# Mcu.net
KiCad netlist of a schematic drawn in Altium Designer
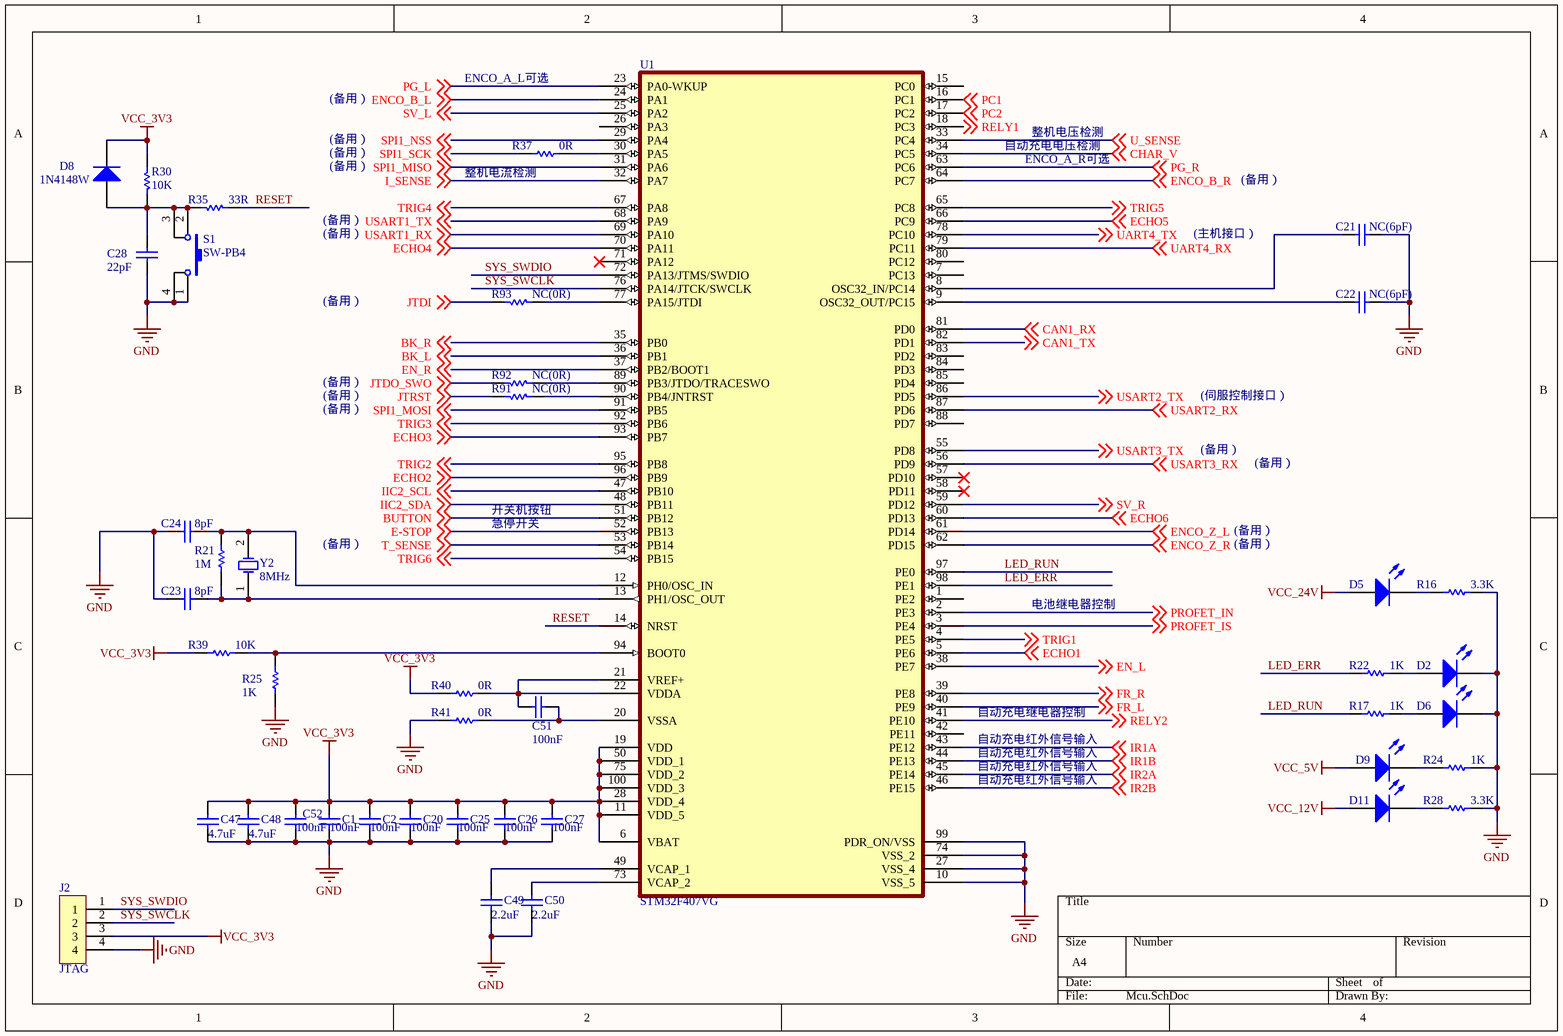
[diagram p0: Mcu.SchDoc]

(export (version "E")
  (design (tool "Eeschema 10.0.6"))
  (components
    (comp (ref "C1")
      (value "100nF")
      (footprint "C0805")
      (description "Capacitor")
      (fields (field (name "Comment") "Cap") (field (name "PUBLISHER") "Altium Limited"))
      (libsource (lib "boocax_schlib") (part "Cap"))
    )
    (comp (ref "C2")
      (value "100nF")
      (footprint "C0805")
      (description "Capacitor")
      (fields (field (name "Comment") "Cap") (field (name "PUBLISHER") "Altium Limited"))
      (libsource (lib "boocax_schlib") (part "Cap"))
    )
    (comp (ref "C20")
      (value "100nF")
      (footprint "C0805")
      (description "Capacitor")
      (fields (field (name "Comment") "Cap") (field (name "PUBLISHER") "Altium Limited"))
      (libsource (lib "boocax_schlib") (part "Cap"))
    )
    (comp (ref "C21")
      (value "NC(6pF)")
      (footprint "C0805")
      (description "Capacitor")
      (fields (field (name "PUBLISHER") "Altium Limited"))
      (libsource (lib "Miscellaneous Devices") (part "Cap"))
    )
    (comp (ref "C22")
      (value "NC(6pF)")
      (footprint "C0805")
      (description "Capacitor")
      (fields (field (name "PUBLISHER") "Altium Limited"))
      (libsource (lib "Miscellaneous Devices") (part "Cap"))
    )
    (comp (ref "C23")
      (value "8pF")
      (footprint "C0805")
      (description "Capacitor")
      (fields (field (name "PUBLISHER") "Altium Limited"))
      (libsource (lib "Miscellaneous Devices") (part "Cap"))
    )
    (comp (ref "C24")
      (value "8pF")
      (footprint "C0805")
      (description "Capacitor")
      (fields (field (name "PUBLISHER") "Altium Limited"))
      (libsource (lib "Miscellaneous Devices") (part "Cap"))
    )
    (comp (ref "C25")
      (value "100nF")
      (footprint "C0805")
      (description "Capacitor")
      (fields (field (name "Comment") "Cap") (field (name "PUBLISHER") "Altium Limited"))
      (libsource (lib "boocax_schlib") (part "Cap"))
    )
    (comp (ref "C26")
      (value "100nF")
      (footprint "C0805")
      (description "Capacitor")
      (fields (field (name "Comment") "Cap") (field (name "PUBLISHER") "Altium Limited"))
      (libsource (lib "boocax_schlib") (part "Cap"))
    )
    (comp (ref "C27")
      (value "100nF")
      (footprint "C0805")
      (description "Capacitor")
      (fields (field (name "Comment") "Cap") (field (name "PUBLISHER") "Altium Limited"))
      (libsource (lib "boocax_schlib") (part "Cap"))
    )
    (comp (ref "C28")
      (value "22pF")
      (footprint "C0805")
      (description "Capacitor")
      (fields (field (name "Comment") "Cap") (field (name "PUBLISHER") "Altium Limited"))
      (libsource (lib "boocax_schlib") (part "Cap"))
    )
    (comp (ref "C47")
      (value "4.7uF")
      (footprint "C0805")
      (description "Capacitor")
      (fields (field (name "Comment") "Cap") (field (name "PUBLISHER") "Altium Limited"))
      (libsource (lib "boocax_schlib") (part "Cap"))
    )
    (comp (ref "C48")
      (value "4.7uF")
      (footprint "C0805")
      (description "Capacitor")
      (fields (field (name "Comment") "Cap") (field (name "PUBLISHER") "Altium Limited"))
      (libsource (lib "boocax_schlib") (part "Cap"))
    )
    (comp (ref "C49")
      (value "2.2uF")
      (footprint "C0805")
      (description "Capacitor")
      (fields (field (name "Comment") "Cap") (field (name "PUBLISHER") "Altium Limited"))
      (libsource (lib "boocax_schlib") (part "Cap"))
    )
    (comp (ref "C50")
      (value "2.2uF")
      (footprint "C0805")
      (description "Capacitor")
      (fields (field (name "Comment") "Cap") (field (name "PUBLISHER") "Altium Limited"))
      (libsource (lib "boocax_schlib") (part "Cap"))
    )
    (comp (ref "C51")
      (value "100nF")
      (footprint "C0805")
      (description "Capacitor")
      (fields (field (name "Comment") "Cap") (field (name "PUBLISHER") "Altium Limited"))
      (libsource (lib "boocax_schlib") (part "Cap"))
    )
    (comp (ref "C52")
      (value "100nF")
      (footprint "C0805")
      (description "Capacitor")
      (fields (field (name "Comment") "Cap") (field (name "PUBLISHER") "Altium Limited"))
      (libsource (lib "boocax_schlib") (part "Cap"))
    )
    (comp (ref "D2")
      (value "LED0")
      (footprint "LED-H-R2.54")
      (description "发光二极管")
      (fields (field (name "PUBLISHER") "Altium Limited"))
      (libsource (lib "founder") (part "LED0"))
    )
    (comp (ref "D5")
      (value "LED0")
      (footprint "LED-H-R2.54")
      (description "发光二极管")
      (fields (field (name "PUBLISHER") "Altium Limited"))
      (libsource (lib "founder") (part "LED0"))
    )
    (comp (ref "D6")
      (value "LED0")
      (footprint "LED-H-R2.54")
      (description "发光二极管")
      (fields (field (name "PUBLISHER") "Altium Limited"))
      (libsource (lib "founder") (part "LED0"))
    )
    (comp (ref "D8")
      (value "1N4148W")
      (footprint "1206")
      (description "二极管")
      (fields (field (name "Comment") "Diode") (field (name "PUBLISHER") "Altium Limited"))
      (libsource (lib "founder") (part "Diode"))
    )
    (comp (ref "D9")
      (value "LED0")
      (footprint "LED-H-R2.54")
      (description "发光二极管")
      (fields (field (name "PUBLISHER") "Altium Limited"))
      (libsource (lib "founder") (part "LED0"))
    )
    (comp (ref "D11")
      (value "LED0")
      (footprint "LED-H-R2.54")
      (description "发光二极管")
      (fields (field (name "PUBLISHER") "Altium Limited"))
      (libsource (lib "founder") (part "LED0"))
    )
    (comp (ref "J2")
      (value "JTAG")
      (footprint "PORT-SIP4-2.54")
      (libsource (lib "boocax_schlib") (part "Conn_1*4_1"))
    )
    (comp (ref "R16")
      (value "3.3K")
      (footprint "R0805")
      (description "Resistor")
      (fields (field (name "Comment") "Res1") (field (name "PUBLISHER") "Altium Limited"))
      (libsource (lib "boocax_schlib") (part "Res1"))
    )
    (comp (ref "R17")
      (value "1K")
      (footprint "R0805")
      (description "Resistor")
      (fields (field (name "Comment") "Res1") (field (name "PUBLISHER") "Altium Limited"))
      (libsource (lib "boocax_schlib") (part "Res1"))
    )
    (comp (ref "R21")
      (value "1M")
      (footprint "R0805")
      (description "Resistor")
      (fields (field (name "Comment") "Res1") (field (name "PUBLISHER") "Altium Limited"))
      (libsource (lib "boocax_schlib") (part "Res1"))
    )
    (comp (ref "R22")
      (value "1K")
      (footprint "R0805")
      (description "Resistor")
      (fields (field (name "Comment") "Res1") (field (name "PUBLISHER") "Altium Limited"))
      (libsource (lib "boocax_schlib") (part "Res1"))
    )
    (comp (ref "R24")
      (value "1K")
      (footprint "R0805")
      (description "Resistor")
      (fields (field (name "Comment") "Res1") (field (name "PUBLISHER") "Altium Limited"))
      (libsource (lib "boocax_schlib") (part "Res1"))
    )
    (comp (ref "R25")
      (value "1K")
      (footprint "R0805")
      (description "Resistor")
      (fields (field (name "Comment") "Res1") (field (name "PUBLISHER") "Altium Limited"))
      (libsource (lib "boocax_schlib") (part "Res1"))
    )
    (comp (ref "R28")
      (value "3.3K")
      (footprint "R0805")
      (description "Resistor")
      (fields (field (name "Comment") "Res1") (field (name "PUBLISHER") "Altium Limited"))
      (libsource (lib "boocax_schlib") (part "Res1"))
    )
    (comp (ref "R30")
      (value "10K")
      (footprint "R0805")
      (description "Resistor")
      (fields (field (name "Comment") "Res1") (field (name "PUBLISHER") "Altium Limited"))
      (libsource (lib "boocax_schlib") (part "Res1"))
    )
    (comp (ref "R35")
      (value "33R")
      (footprint "R0805")
      (description "Resistor")
      (fields (field (name "Comment") "Res1") (field (name "PUBLISHER") "Altium Limited"))
      (libsource (lib "boocax_schlib") (part "Res1"))
    )
    (comp (ref "R37")
      (value "0R")
      (footprint "R0805")
      (description "Resistor")
      (fields (field (name "Comment") "Res1") (field (name "PUBLISHER") "Altium Limited"))
      (libsource (lib "boocax_schlib") (part "Res1"))
    )
    (comp (ref "R39")
      (value "10K")
      (footprint "R0805")
      (description "Resistor")
      (fields (field (name "Comment") "Res1") (field (name "PUBLISHER") "Altium Limited"))
      (libsource (lib "boocax_schlib") (part "Res1"))
    )
    (comp (ref "R40")
      (value "0R")
      (footprint "R0805")
      (description "Resistor")
      (fields (field (name "Comment") "Res1") (field (name "PUBLISHER") "Altium Limited"))
      (libsource (lib "boocax_schlib") (part "Res1"))
    )
    (comp (ref "R41")
      (value "0R")
      (footprint "R0805")
      (description "Resistor")
      (fields (field (name "Comment") "Res1") (field (name "PUBLISHER") "Altium Limited"))
      (libsource (lib "boocax_schlib") (part "Res1"))
    )
    (comp (ref "R91")
      (value "NC(0R)")
      (footprint "R0805")
      (description "Resistor")
      (fields (field (name "Comment") "Res1") (field (name "PUBLISHER") "Altium Limited"))
      (libsource (lib "boocax_schlib") (part "Res1"))
    )
    (comp (ref "R92")
      (value "NC(0R)")
      (footprint "R0805")
      (description "Resistor")
      (fields (field (name "Comment") "Res1") (field (name "PUBLISHER") "Altium Limited"))
      (libsource (lib "boocax_schlib") (part "Res1"))
    )
    (comp (ref "R93")
      (value "NC(0R)")
      (footprint "R0805")
      (description "Resistor")
      (fields (field (name "Comment") "Res1") (field (name "PUBLISHER") "Altium Limited"))
      (libsource (lib "boocax_schlib") (part "Res1"))
    )
    (comp (ref "S1")
      (value "SW-PB4")
      (footprint "RESET-SMD-1O4")
      (description "微动开关")
      (fields (field (name "PUBLISHER") "Altium Limited"))
      (libsource (lib "boocax_schlib") (part "SW-PB4"))
    )
    (comp (ref "U1")
      (value "STM32F407VG")
      (footprint "boocax_schlib:100T1_N")
      (libsource (lib "boocax_schlib") (part "STM32F407VG"))
    )
    (comp (ref "Y2")
      (value "8MHz")
      (footprint "CLK_3.1")
      (description "X1A0000610030xx")
      (fields (field (name "PUBLISHER") "Altium Limited"))
      (libsource (lib "Miscellaneous Devices") (part "XTAL"))
    )
  )
  (nets
    (net (code "1") (name "/LED_ERR") (class "Default")
      (node (ref "R22") (pin "2") (pinfunction "2_2") (pintype "passive"))
      (node (ref "U1") (pin "98") (pinfunction "PE1_98") (pintype "bidirectional"))
    )
    (net (code "2") (name "/LED_RUN") (class "Default")
      (node (ref "R17") (pin "2") (pinfunction "2_2") (pintype "passive"))
      (node (ref "U1") (pin "97") (pinfunction "PE0_97") (pintype "bidirectional"))
    )
    (net (code "3") (name "/RESET") (class "Default")
      (node (ref "R35") (pin "1") (pinfunction "1_1") (pintype "passive"))
      (node (ref "U1") (pin "14") (pinfunction "NRST_14") (pintype "bidirectional"))
    )
    (net (code "4") (name "/SYS_SWCLK") (class "Default")
      (node (ref "J2") (pin "2") (pinfunction "2_2") (pintype "passive"))
      (node (ref "U1") (pin "76") (pinfunction "PA14/JTCK/SWCLK_76") (pintype "bidirectional"))
    )
    (net (code "5") (name "/SYS_SWDIO") (class "Default")
      (node (ref "J2") (pin "1") (pinfunction "1_1") (pintype "passive"))
      (node (ref "U1") (pin "72") (pinfunction "PA13/JTMS/SWDIO_72") (pintype "bidirectional"))
    )
    (net (code "6") (name "BK_L") (class "Default")
      (node (ref "U1") (pin "36") (pinfunction "PB1_36") (pintype "bidirectional"))
    )
    (net (code "7") (name "BK_R") (class "Default")
      (node (ref "U1") (pin "35") (pinfunction "PB0_35") (pintype "bidirectional"))
    )
    (net (code "8") (name "BUTTON") (class "Default")
      (node (ref "U1") (pin "51") (pinfunction "PB12_51") (pintype "bidirectional"))
    )
    (net (code "9") (name "CAN1_RX") (class "Default")
      (node (ref "U1") (pin "81") (pinfunction "PD0_81") (pintype "bidirectional"))
    )
    (net (code "10") (name "CAN1_TX") (class "Default")
      (node (ref "U1") (pin "82") (pinfunction "PD1_82") (pintype "bidirectional"))
    )
    (net (code "11") (name "CHAR_V") (class "Default")
      (node (ref "U1") (pin "34") (pinfunction "PC5_34") (pintype "bidirectional"))
    )
    (net (code "12") (name "E-STOP") (class "Default")
      (node (ref "U1") (pin "52") (pinfunction "PB13_52") (pintype "bidirectional"))
    )
    (net (code "13") (name "ECHO1") (class "Default")
      (node (ref "U1") (pin "5") (pinfunction "PE6_5") (pintype "bidirectional"))
    )
    (net (code "14") (name "ECHO2") (class "Default")
      (node (ref "U1") (pin "96") (pinfunction "PB9_96") (pintype "bidirectional"))
    )
    (net (code "15") (name "ECHO3") (class "Default")
      (node (ref "U1") (pin "93") (pinfunction "PB7_93") (pintype "bidirectional"))
    )
    (net (code "16") (name "ECHO4") (class "Default")
      (node (ref "U1") (pin "70") (pinfunction "PA11_70") (pintype "bidirectional"))
    )
    (net (code "17") (name "ECHO5") (class "Default")
      (node (ref "U1") (pin "66") (pinfunction "PC9_66") (pintype "bidirectional"))
    )
    (net (code "18") (name "ECHO6") (class "Default")
      (node (ref "U1") (pin "60") (pinfunction "PD13_60") (pintype "bidirectional"))
    )
    (net (code "19") (name "ENCO_B_L") (class "Default")
      (node (ref "U1") (pin "24") (pinfunction "PA1_24") (pintype "bidirectional"))
    )
    (net (code "20") (name "ENCO_B_R") (class "Default")
      (node (ref "U1") (pin "64") (pinfunction "PC7_64") (pintype "bidirectional"))
    )
    (net (code "21") (name "ENCO_Z_L") (class "Default")
      (node (ref "U1") (pin "61") (pinfunction "PD14_61") (pintype "bidirectional"))
    )
    (net (code "22") (name "ENCO_Z_R") (class "Default")
      (node (ref "U1") (pin "62") (pinfunction "PD15_62") (pintype "bidirectional"))
    )
    (net (code "23") (name "EN_L") (class "Default")
      (node (ref "U1") (pin "38") (pinfunction "PE7_38") (pintype "bidirectional"))
    )
    (net (code "24") (name "EN_R") (class "Default")
      (node (ref "U1") (pin "37") (pinfunction "PB2/BOOT1_37") (pintype "bidirectional"))
    )
    (net (code "25") (name "FR_L") (class "Default")
      (node (ref "U1") (pin "40") (pinfunction "PE9_40") (pintype "bidirectional"))
    )
    (net (code "26") (name "FR_R") (class "Default")
      (node (ref "U1") (pin "39") (pinfunction "PE8_39") (pintype "bidirectional"))
    )
    (net (code "27") (name "GND") (class "Default")
      (node (ref "C1") (pin "2") (pinfunction "2_2") (pintype "passive"))
      (node (ref "C2") (pin "2") (pinfunction "2_2") (pintype "passive"))
      (node (ref "C20") (pin "2") (pinfunction "2_2") (pintype "passive"))
      (node (ref "C21") (pin "1") (pinfunction "1_1") (pintype "passive"))
      (node (ref "C22") (pin "1") (pinfunction "1_1") (pintype "passive"))
      (node (ref "C23") (pin "2") (pinfunction "2_2") (pintype "passive"))
      (node (ref "C24") (pin "2") (pinfunction "2_2") (pintype "passive"))
      (node (ref "C25") (pin "2") (pinfunction "2_2") (pintype "passive"))
      (node (ref "C26") (pin "2") (pinfunction "2_2") (pintype "passive"))
      (node (ref "C27") (pin "2") (pinfunction "2_2") (pintype "passive"))
      (node (ref "C28") (pin "1") (pinfunction "1_1") (pintype "passive"))
      (node (ref "C47") (pin "2") (pinfunction "2_2") (pintype "passive"))
      (node (ref "C48") (pin "2") (pinfunction "2_2") (pintype "passive"))
      (node (ref "C49") (pin "2") (pinfunction "2_2") (pintype "passive"))
      (node (ref "C50") (pin "2") (pinfunction "2_2") (pintype "passive"))
      (node (ref "C52") (pin "2") (pinfunction "2_2") (pintype "passive"))
      (node (ref "D2") (pin "2") (pinfunction "K_2") (pintype "passive"))
      (node (ref "D6") (pin "2") (pinfunction "K_2") (pintype "passive"))
      (node (ref "J2") (pin "4") (pinfunction "4_4") (pintype "passive"))
      (node (ref "R16") (pin "1") (pinfunction "1_1") (pintype "passive"))
      (node (ref "R24") (pin "1") (pinfunction "1_1") (pintype "passive"))
      (node (ref "R25") (pin "1") (pinfunction "1_1") (pintype "passive"))
      (node (ref "R28") (pin "1") (pinfunction "1_1") (pintype "passive"))
      (node (ref "R41") (pin "2") (pinfunction "2_2") (pintype "passive"))
      (node (ref "S1") (pin "1") (pinfunction "1_1") (pintype "passive"))
      (node (ref "S1") (pin "4") (pinfunction "4_4") (pintype "passive"))
      (node (ref "U1") (pin "10") (pinfunction "VSS_5_10") (pintype "passive"))
      (node (ref "U1") (pin "27") (pinfunction "VSS_4_27") (pintype "passive"))
      (node (ref "U1") (pin "74") (pinfunction "VSS_2_74") (pintype "passive"))
      (node (ref "U1") (pin "99") (pinfunction "PDR_ON/VSS_99") (pintype "power_in"))
    )
    (net (code "28") (name "IIC2_SCL") (class "Default")
      (node (ref "U1") (pin "47") (pinfunction "PB10_47") (pintype "bidirectional"))
    )
    (net (code "29") (name "IIC2_SDA") (class "Default")
      (node (ref "U1") (pin "48") (pinfunction "PB11_48") (pintype "bidirectional"))
    )
    (net (code "30") (name "IR1A") (class "Default")
      (node (ref "U1") (pin "43") (pinfunction "PE12_43") (pintype "bidirectional"))
    )
    (net (code "31") (name "IR1B") (class "Default")
      (node (ref "U1") (pin "44") (pinfunction "PE13_44") (pintype "bidirectional"))
    )
    (net (code "32") (name "IR2A") (class "Default")
      (node (ref "U1") (pin "45") (pinfunction "PE14_45") (pintype "bidirectional"))
    )
    (net (code "33") (name "IR2B") (class "Default")
      (node (ref "U1") (pin "46") (pinfunction "PE15_46") (pintype "bidirectional"))
    )
    (net (code "34") (name "I_SENSE") (class "Default")
      (node (ref "U1") (pin "32") (pinfunction "PA7_32") (pintype "bidirectional"))
    )
    (net (code "35") (name "JTDI") (class "Default")
      (node (ref "R93") (pin "2") (pinfunction "2_2") (pintype "passive"))
    )
    (net (code "36") (name "JTDO_SWO") (class "Default")
      (node (ref "R92") (pin "2") (pinfunction "2_2") (pintype "passive"))
    )
    (net (code "37") (name "JTRST") (class "Default")
      (node (ref "R91") (pin "2") (pinfunction "2_2") (pintype "passive"))
    )
    (net (code "38") (name "Net-(D2-A)") (class "Default")
      (node (ref "D2") (pin "1") (pinfunction "A_1") (pintype "passive"))
      (node (ref "R22") (pin "1") (pinfunction "1_1") (pintype "passive"))
    )
    (net (code "39") (name "Net-(D5-K)") (class "Default")
      (node (ref "D5") (pin "2") (pinfunction "K_2") (pintype "passive"))
      (node (ref "R16") (pin "2") (pinfunction "2_2") (pintype "passive"))
    )
    (net (code "40") (name "Net-(D6-A)") (class "Default")
      (node (ref "D6") (pin "1") (pinfunction "A_1") (pintype "passive"))
      (node (ref "R17") (pin "1") (pinfunction "1_1") (pintype "passive"))
    )
    (net (code "41") (name "Net-(D8-A)") (class "Default")
      (node (ref "C28") (pin "2") (pinfunction "2_2") (pintype "passive"))
      (node (ref "D8") (pin "1") (pinfunction "A_1") (pintype "passive"))
      (node (ref "R30") (pin "1") (pinfunction "1_1") (pintype "passive"))
      (node (ref "R35") (pin "2") (pinfunction "2_2") (pintype "passive"))
      (node (ref "S1") (pin "2") (pinfunction "2_2") (pintype "passive"))
      (node (ref "S1") (pin "3") (pinfunction "3_3") (pintype "passive"))
    )
    (net (code "42") (name "Net-(D9-K)") (class "Default")
      (node (ref "D9") (pin "2") (pinfunction "K_2") (pintype "passive"))
      (node (ref "R24") (pin "2") (pinfunction "2_2") (pintype "passive"))
    )
    (net (code "43") (name "Net-(D11-K)") (class "Default")
      (node (ref "D11") (pin "2") (pinfunction "K_2") (pintype "passive"))
      (node (ref "R28") (pin "2") (pinfunction "2_2") (pintype "passive"))
    )
    (net (code "44") (name "Net-(U1-BOOT0)") (class "Default")
      (node (ref "R25") (pin "2") (pinfunction "2_2") (pintype "passive"))
      (node (ref "R39") (pin "1") (pinfunction "1_1") (pintype "passive"))
      (node (ref "U1") (pin "94") (pinfunction "BOOT0_94") (pintype "input"))
    )
    (net (code "45") (name "Net-(U1-OSC32_IN{slash}PC14)") (class "Default")
      (node (ref "C21") (pin "2") (pinfunction "2_2") (pintype "passive"))
      (node (ref "U1") (pin "8") (pinfunction "OSC32_IN/PC14_8") (pintype "bidirectional"))
    )
    (net (code "46") (name "Net-(U1-OSC32_OUT{slash}PC15)") (class "Default")
      (node (ref "C22") (pin "2") (pinfunction "2_2") (pintype "passive"))
      (node (ref "U1") (pin "9") (pinfunction "OSC32_OUT/PC15_9") (pintype "bidirectional"))
    )
    (net (code "47") (name "Net-(U1-PA5)") (class "Default")
      (node (ref "R37") (pin "1") (pinfunction "1_1") (pintype "passive"))
      (node (ref "U1") (pin "30") (pinfunction "PA5_30") (pintype "bidirectional"))
    )
    (net (code "48") (name "Net-(U1-PA15{slash}JTDI)") (class "Default")
      (node (ref "R93") (pin "1") (pinfunction "1_1") (pintype "passive"))
      (node (ref "U1") (pin "77") (pinfunction "PA15/JTDI_77") (pintype "bidirectional"))
    )
    (net (code "49") (name "Net-(U1-PB3{slash}JTDO{slash}TRACESWO)") (class "Default")
      (node (ref "R92") (pin "1") (pinfunction "1_1") (pintype "passive"))
      (node (ref "U1") (pin "89") (pinfunction "PB3/JTDO/TRACESWO_89") (pintype "bidirectional"))
    )
    (net (code "50") (name "Net-(U1-PB4{slash}JNTRST)") (class "Default")
      (node (ref "R91") (pin "1") (pinfunction "1_1") (pintype "passive"))
      (node (ref "U1") (pin "90") (pinfunction "PB4/JNTRST_90") (pintype "bidirectional"))
    )
    (net (code "51") (name "Net-(U1-PH0{slash}OSC_IN)") (class "Default")
      (node (ref "C24") (pin "1") (pinfunction "1_1") (pintype "passive"))
      (node (ref "R21") (pin "2") (pinfunction "2_2") (pintype "passive"))
      (node (ref "U1") (pin "12") (pinfunction "PH0/OSC_IN_12") (pintype "input"))
      (node (ref "Y2") (pin "2") (pinfunction "OSC2_2") (pintype "passive"))
    )
    (net (code "52") (name "Net-(U1-PH1{slash}OSC_OUT)") (class "Default")
      (node (ref "C23") (pin "1") (pinfunction "1_1") (pintype "passive"))
      (node (ref "R21") (pin "1") (pinfunction "1_1") (pintype "passive"))
      (node (ref "U1") (pin "13") (pinfunction "PH1/OSC_OUT_13") (pintype "output"))
      (node (ref "Y2") (pin "1") (pinfunction "OSC1_1") (pintype "passive"))
    )
    (net (code "53") (name "Net-(U1-VCAP_1)") (class "Default")
      (node (ref "C49") (pin "1") (pinfunction "1_1") (pintype "passive"))
      (node (ref "U1") (pin "49") (pinfunction "VCAP_1_49") (pintype "power_in"))
    )
    (net (code "54") (name "Net-(U1-VCAP_2)") (class "Default")
      (node (ref "C50") (pin "1") (pinfunction "1_1") (pintype "passive"))
      (node (ref "U1") (pin "73") (pinfunction "VCAP_2_73") (pintype "power_in"))
    )
    (net (code "55") (name "Net-(U1-VDDA)") (class "Default")
      (node (ref "C51") (pin "1") (pinfunction "1_1") (pintype "passive"))
      (node (ref "R40") (pin "1") (pinfunction "1_1") (pintype "passive"))
      (node (ref "U1") (pin "21") (pinfunction "VREF+_21") (pintype "power_in"))
      (node (ref "U1") (pin "22") (pinfunction "VDDA_22") (pintype "power_in"))
    )
    (net (code "56") (name "Net-(U1-VSSA)") (class "Default")
      (node (ref "C51") (pin "2") (pinfunction "2_2") (pintype "passive"))
      (node (ref "R41") (pin "1") (pinfunction "1_1") (pintype "passive"))
      (node (ref "U1") (pin "20") (pinfunction "VSSA_20") (pintype "power_in"))
    )
    (net (code "57") (name "PC1") (class "Default")
      (node (ref "U1") (pin "16") (pinfunction "PC1_16") (pintype "bidirectional"))
    )
    (net (code "58") (name "PC2") (class "Default")
      (node (ref "U1") (pin "17") (pinfunction "PC2_17") (pintype "bidirectional"))
    )
    (net (code "59") (name "PG_L") (class "Default")
      (node (ref "U1") (pin "23") (pinfunction "PA0-WKUP_23") (pintype "bidirectional"))
    )
    (net (code "60") (name "PG_R") (class "Default")
      (node (ref "U1") (pin "63") (pinfunction "PC6_63") (pintype "bidirectional"))
    )
    (net (code "61") (name "PROFET_IN") (class "Default")
      (node (ref "U1") (pin "2") (pinfunction "PE3_2") (pintype "bidirectional"))
    )
    (net (code "62") (name "PROFET_IS") (class "Default")
      (node (ref "U1") (pin "3") (pinfunction "PE4_3") (pintype "bidirectional"))
    )
    (net (code "63") (name "RELY1") (class "Default")
      (node (ref "U1") (pin "18") (pinfunction "PC3_18") (pintype "bidirectional"))
    )
    (net (code "64") (name "RELY2") (class "Default")
      (node (ref "U1") (pin "41") (pinfunction "PE10_41") (pintype "bidirectional"))
    )
    (net (code "65") (name "SPI1_MISO") (class "Default")
      (node (ref "U1") (pin "31") (pinfunction "PA6_31") (pintype "bidirectional"))
    )
    (net (code "66") (name "SPI1_MOSI") (class "Default")
      (node (ref "U1") (pin "91") (pinfunction "PB5_91") (pintype "bidirectional"))
    )
    (net (code "67") (name "SPI1_NSS") (class "Default")
      (node (ref "U1") (pin "29") (pinfunction "PA4_29") (pintype "bidirectional"))
    )
    (net (code "68") (name "SPI1_SCK") (class "Default")
      (node (ref "R37") (pin "2") (pinfunction "2_2") (pintype "passive"))
    )
    (net (code "69") (name "SV_L") (class "Default")
      (node (ref "U1") (pin "25") (pinfunction "PA2_25") (pintype "bidirectional"))
    )
    (net (code "70") (name "SV_R") (class "Default")
      (node (ref "U1") (pin "59") (pinfunction "PD12_59") (pintype "bidirectional"))
    )
    (net (code "71") (name "TRIG1") (class "Default")
      (node (ref "U1") (pin "4") (pinfunction "PE5_4") (pintype "bidirectional"))
    )
    (net (code "72") (name "TRIG2") (class "Default")
      (node (ref "U1") (pin "95") (pinfunction "PB8_95") (pintype "bidirectional"))
    )
    (net (code "73") (name "TRIG3") (class "Default")
      (node (ref "U1") (pin "92") (pinfunction "PB6_92") (pintype "bidirectional"))
    )
    (net (code "74") (name "TRIG4") (class "Default")
      (node (ref "U1") (pin "67") (pinfunction "PA8_67") (pintype "bidirectional"))
    )
    (net (code "75") (name "TRIG5") (class "Default")
      (node (ref "U1") (pin "65") (pinfunction "PC8_65") (pintype "bidirectional"))
    )
    (net (code "76") (name "TRIG6") (class "Default")
      (node (ref "U1") (pin "54") (pinfunction "PB15_54") (pintype "bidirectional"))
    )
    (net (code "77") (name "T_SENSE") (class "Default")
      (node (ref "U1") (pin "53") (pinfunction "PB14_53") (pintype "bidirectional"))
    )
    (net (code "78") (name "UART4_RX") (class "Default")
      (node (ref "U1") (pin "79") (pinfunction "PC11_79") (pintype "bidirectional"))
    )
    (net (code "79") (name "UART4_TX") (class "Default")
      (node (ref "U1") (pin "78") (pinfunction "PC10_78") (pintype "bidirectional"))
    )
    (net (code "80") (name "USART1_RX") (class "Default")
      (node (ref "U1") (pin "69") (pinfunction "PA10_69") (pintype "bidirectional"))
    )
    (net (code "81") (name "USART1_TX") (class "Default")
      (node (ref "U1") (pin "68") (pinfunction "PA9_68") (pintype "bidirectional"))
    )
    (net (code "82") (name "USART2_RX") (class "Default")
      (node (ref "U1") (pin "87") (pinfunction "PD6_87") (pintype "bidirectional"))
    )
    (net (code "83") (name "USART2_TX") (class "Default")
      (node (ref "U1") (pin "86") (pinfunction "PD5_86") (pintype "bidirectional"))
    )
    (net (code "84") (name "USART3_RX") (class "Default")
      (node (ref "U1") (pin "56") (pinfunction "PD9_56") (pintype "bidirectional"))
    )
    (net (code "85") (name "USART3_TX") (class "Default")
      (node (ref "U1") (pin "55") (pinfunction "PD8_55") (pintype "bidirectional"))
    )
    (net (code "86") (name "U_SENSE") (class "Default")
      (node (ref "U1") (pin "33") (pinfunction "PC4_33") (pintype "bidirectional"))
    )
    (net (code "87") (name "VCC_3V3") (class "Default")
      (node (ref "C1") (pin "1") (pinfunction "1_1") (pintype "passive"))
      (node (ref "C2") (pin "1") (pinfunction "1_1") (pintype "passive"))
      (node (ref "C20") (pin "1") (pinfunction "1_1") (pintype "passive"))
      (node (ref "C25") (pin "1") (pinfunction "1_1") (pintype "passive"))
      (node (ref "C26") (pin "1") (pinfunction "1_1") (pintype "passive"))
      (node (ref "C27") (pin "1") (pinfunction "1_1") (pintype "passive"))
      (node (ref "C47") (pin "1") (pinfunction "1_1") (pintype "passive"))
      (node (ref "C48") (pin "1") (pinfunction "1_1") (pintype "passive"))
      (node (ref "C52") (pin "1") (pinfunction "1_1") (pintype "passive"))
      (node (ref "D8") (pin "2") (pinfunction "K_2") (pintype "passive"))
      (node (ref "J2") (pin "3") (pinfunction "3_3") (pintype "passive"))
      (node (ref "R30") (pin "2") (pinfunction "2_2") (pintype "passive"))
      (node (ref "R39") (pin "2") (pinfunction "2_2") (pintype "passive"))
      (node (ref "R40") (pin "2") (pinfunction "2_2") (pintype "passive"))
      (node (ref "U1") (pin "100") (pinfunction "VDD_3_100") (pintype "power_in"))
      (node (ref "U1") (pin "11") (pinfunction "VDD_5_11") (pintype "power_in"))
      (node (ref "U1") (pin "19") (pinfunction "VDD_19") (pintype "power_in"))
      (node (ref "U1") (pin "28") (pinfunction "VDD_4_28") (pintype "power_in"))
      (node (ref "U1") (pin "50") (pinfunction "VDD_1_50") (pintype "power_in"))
      (node (ref "U1") (pin "6") (pinfunction "VBAT_6") (pintype "power_in"))
      (node (ref "U1") (pin "75") (pinfunction "VDD_2_75") (pintype "power_in"))
    )
    (net (code "88") (name "VCC_5V") (class "Default")
      (node (ref "D9") (pin "1") (pinfunction "A_1") (pintype "passive"))
    )
    (net (code "89") (name "VCC_12V") (class "Default")
      (node (ref "D11") (pin "1") (pinfunction "A_1") (pintype "passive"))
    )
    (net (code "90") (name "VCC_24V") (class "Default")
      (node (ref "D5") (pin "1") (pinfunction "A_1") (pintype "passive"))
    )
    (net (code "91") (name "unconnected-(U1-PA3-Pad26)") (class "Default")
      (node (ref "U1") (pin "26") (pinfunction "PA3_26") (pintype "bidirectional"))
    )
    (net (code "92") (name "unconnected-(U1-PA12-Pad71)") (class "Default")
      (node (ref "U1") (pin "71") (pinfunction "PA12_71") (pintype "bidirectional+no_connect"))
    )
    (net (code "93") (name "unconnected-(U1-PC0-Pad15)") (class "Default")
      (node (ref "U1") (pin "15") (pinfunction "PC0_15") (pintype "bidirectional"))
    )
    (net (code "94") (name "unconnected-(U1-PC12-Pad80)") (class "Default")
      (node (ref "U1") (pin "80") (pinfunction "PC12_80") (pintype "bidirectional"))
    )
    (net (code "95") (name "unconnected-(U1-PC13-Pad7)") (class "Default")
      (node (ref "U1") (pin "7") (pinfunction "PC13_7") (pintype "bidirectional"))
    )
    (net (code "96") (name "unconnected-(U1-PD2-Pad83)") (class "Default")
      (node (ref "U1") (pin "83") (pinfunction "PD2_83") (pintype "bidirectional"))
    )
    (net (code "97") (name "unconnected-(U1-PD3-Pad84)") (class "Default")
      (node (ref "U1") (pin "84") (pinfunction "PD3_84") (pintype "bidirectional"))
    )
    (net (code "98") (name "unconnected-(U1-PD4-Pad85)") (class "Default")
      (node (ref "U1") (pin "85") (pinfunction "PD4_85") (pintype "bidirectional"))
    )
    (net (code "99") (name "unconnected-(U1-PD7-Pad88)") (class "Default")
      (node (ref "U1") (pin "88") (pinfunction "PD7_88") (pintype "bidirectional"))
    )
    (net (code "100") (name "unconnected-(U1-PD10-Pad57)") (class "Default")
      (node (ref "U1") (pin "57") (pinfunction "PD10_57") (pintype "bidirectional+no_connect"))
    )
    (net (code "101") (name "unconnected-(U1-PD11-Pad58)") (class "Default")
      (node (ref "U1") (pin "58") (pinfunction "PD11_58") (pintype "bidirectional+no_connect"))
    )
    (net (code "102") (name "unconnected-(U1-PE2-Pad1)") (class "Default")
      (node (ref "U1") (pin "1") (pinfunction "PE2_1") (pintype "bidirectional"))
    )
    (net (code "103") (name "unconnected-(U1-PE11-Pad42)") (class "Default")
      (node (ref "U1") (pin "42") (pinfunction "PE11_42") (pintype "bidirectional"))
    )
  )
)
